# main.net
KiCad netlist of a schematic drawn in Altium Designer
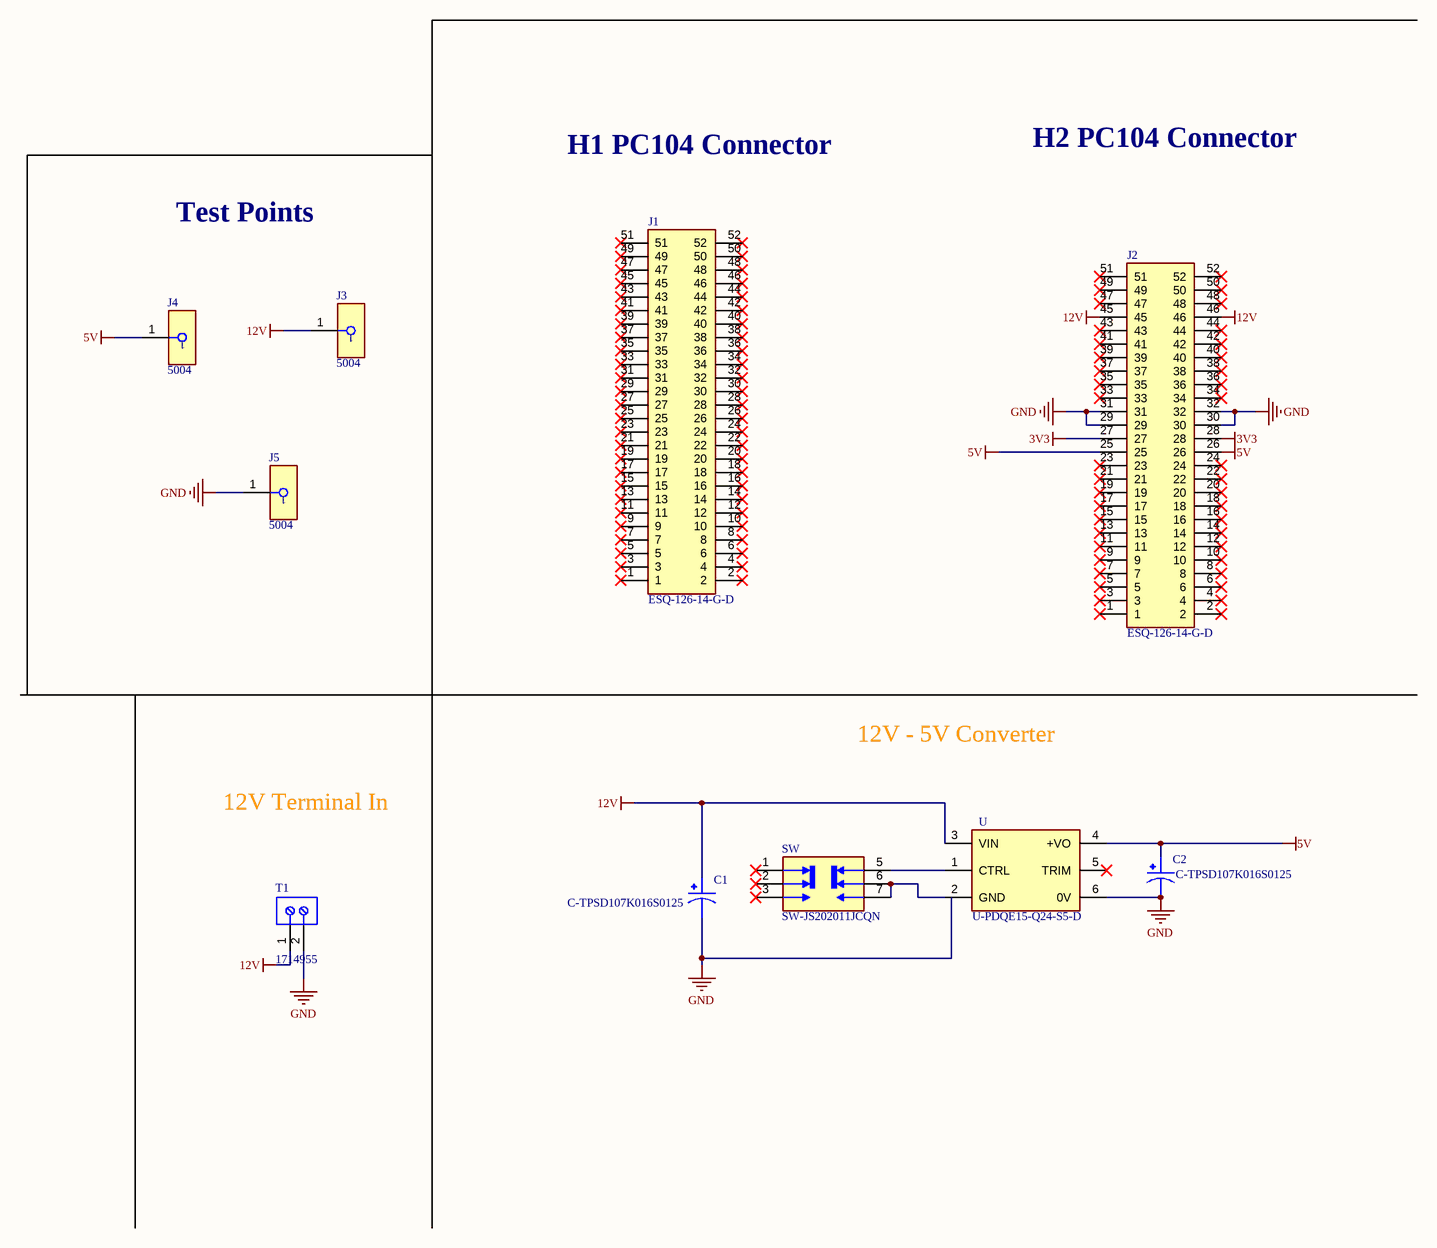
[diagram p0: main.SchDoc]

(export (version "E")
  (design (tool "Eeschema 10.0.6"))
  (components
    (comp (ref "C1")
      (value "C-TPSD107K016S0125")
      (footprint "C-TPSD107K016S0125")
      (description "CAP TANT 100UF 10% 16V 2917")
      (fields (field (name "MANUFACTURER") "KYOCERA AVX") (field (name "DIGI-KEY PART #") "478-9141-1-ND"))
      (libsource (lib "Netra_OBC_aux_power_board") (part "C-TPSD107K016S0125"))
    )
    (comp (ref "C2")
      (value "C-TPSD107K016S0125")
      (footprint "C-TPSD107K016S0125")
      (description "CAP TANT 100UF 10% 16V 2917")
      (fields (field (name "MANUFACTURER") "KYOCERA AVX") (field (name "DIGI-KEY PART #") "478-9141-1-ND"))
      (libsource (lib "Netra_OBC_aux_power_board") (part "C-TPSD107K016S0125"))
    )
    (comp (ref "J1")
      (value "ESQ-126-14-G-D")
      (footprint "SAMTEC_ESQ-126-14-G-D")
      (description "CONN SOCKET 52POS 0.1 GOLD PCB")
      (fields (field (name "MANUFACTURER") "Samtec Inc.") (field (name "DISTRIBUTOR PART #") "SAM11114-ND"))
      (libsource (lib "Netra_OBC_aux_power_board") (part "J-ESQ-126-14-G-D"))
    )
    (comp (ref "J2")
      (value "ESQ-126-14-G-D")
      (footprint "SAMTEC_ESQ-126-14-G-D")
      (description "CONN SOCKET 52POS 0.1 GOLD PCB")
      (fields (field (name "MANUFACTURER") "Samtec Inc.") (field (name "DISTRIBUTOR PART #") "SAM11114-ND"))
      (libsource (lib "Netra_OBC_aux_power_board") (part "J-ESQ-126-14-G-D"))
    )
    (comp (ref "J3")
      (value "5004")
      (footprint "FP-5004-MFG")
      (description "PC TEST POINT MINIATURE YELLOW")
      (fields
        (field (name "MANUFACTURER") "Keystone Electronics")
        (field (name "OCTOPART") "https://octopart.com/5004-keystone-28591")
      )
      (libsource (lib "Netra_OBC_aux_power_board") (part "CMP-2000-05575-2"))
    )
    (comp (ref "J4")
      (value "5004")
      (footprint "FP-5004-MFG")
      (description "PC TEST POINT MINIATURE YELLOW")
      (fields
        (field (name "MANUFACTURER") "Keystone Electronics")
        (field (name "OCTOPART") "https://octopart.com/5004-keystone-28591")
      )
      (libsource (lib "Netra_OBC_aux_power_board") (part "CMP-2000-05575-2"))
    )
    (comp (ref "J5")
      (value "5004")
      (footprint "FP-5004-MFG")
      (description "PC TEST POINT MINIATURE YELLOW")
      (fields
        (field (name "MANUFACTURER") "Keystone Electronics")
        (field (name "OCTOPART") "https://octopart.com/5004-keystone-28591")
      )
      (libsource (lib "Netra_OBC_aux_power_board") (part "CMP-2000-05575-2"))
    )
    (comp (ref "SW")
      (value "SW-JS202011JCQN")
      (footprint "SW-JS202011JCQN")
      (description "SWITCH SLIDE DPDT 300MA 6V")
      (fields
        (field (name "DISTRIBUTOR PART #") "CKN10723CT-ND")
        (field (name "MANUFACTURER PART #") "JS202011JCQN")
      )
      (libsource (lib "Netra_OBC_aux_power_board") (part "SW-JS202011JCQN"))
    )
    (comp (ref "T1")
      (value "1714955")
      (footprint "PHOE-1714955_V")
      (description "PC Terminal Block, Pitch 6.35 mm, 1 x 2 Position, Height 21.5 mm, Tail Lenght 5.1 mm, RoHS, Bulk")
      (fields (field (name "MANUFACTURER") "Phoenix Contact"))
      (libsource (lib "Altium Content Vault") (part "CN-1P-F-TB2"))
    )
    (comp (ref "U")
      (value "U-PDQE15-Q24-S5-D")
      (footprint "U-PDQE15-Q48-D5-D")
      (description "15 W, 4:1 Input Range, Single/Dual Regulated Output, DIP, 1500 Vdc Isolation, Dc-Dc Converter")
      (fields
        (field (name "MANUFACTUER PART #") "PDQE15-Q24-S5-D")
        (field (name "DISTRIBUTOR PART #") "102-6253-ND")
      )
      (libsource (lib "Netra_OBC_aux_power_board") (part "U-PDQE15-Q24-S5-D"))
    )
  )
  (nets
    (net (code "1") (name "3V3") (class "Default")
      (node (ref "J2") (pin "27") (pinfunction "27_27") (pintype "passive"))
      (node (ref "J2") (pin "28") (pinfunction "28_28") (pintype "passive"))
    )
    (net (code "2") (name "5V") (class "Default")
      (node (ref "C2") (pin "1") (pinfunction "1_1") (pintype "passive"))
      (node (ref "J2") (pin "25") (pinfunction "25_25") (pintype "passive"))
      (node (ref "J2") (pin "26") (pinfunction "26_26") (pintype "passive"))
      (node (ref "J4") (pin "1") (pinfunction "1_1") (pintype "passive"))
      (node (ref "U") (pin "4") (pinfunction "+VO_4") (pintype "passive"))
    )
    (net (code "3") (name "12V") (class "Default")
      (node (ref "C1") (pin "1") (pinfunction "1_1") (pintype "passive"))
      (node (ref "J2") (pin "45") (pinfunction "45_45") (pintype "passive"))
      (node (ref "J2") (pin "46") (pinfunction "46_46") (pintype "passive"))
      (node (ref "J3") (pin "1") (pinfunction "1_1") (pintype "passive"))
      (node (ref "T1") (pin "1") (pinfunction "1_1") (pintype "passive"))
      (node (ref "U") (pin "3") (pinfunction "VIN_3") (pintype "passive"))
    )
    (net (code "4") (name "GND") (class "Default")
      (node (ref "C1") (pin "2") (pinfunction "2_2") (pintype "passive"))
      (node (ref "C2") (pin "2") (pinfunction "2_2") (pintype "passive"))
      (node (ref "J2") (pin "29") (pinfunction "29_29") (pintype "passive"))
      (node (ref "J2") (pin "30") (pinfunction "30_30") (pintype "passive"))
      (node (ref "J2") (pin "31") (pinfunction "31_31") (pintype "passive"))
      (node (ref "J2") (pin "32") (pinfunction "32_32") (pintype "passive"))
      (node (ref "J5") (pin "1") (pinfunction "1_1") (pintype "passive"))
      (node (ref "T1") (pin "2") (pinfunction "2_2") (pintype "passive"))
      (node (ref "U") (pin "6") (pinfunction "0V_6") (pintype "passive"))
    )
    (net (code "5") (name "Net-(U-CTRL)") (class "Default")
      (node (ref "SW") (pin "5") (pinfunction "5_5") (pintype "passive"))
      (node (ref "U") (pin "1") (pinfunction "CTRL_1") (pintype "passive"))
    )
    (net (code "6") (name "Net-(U-GND)") (class "Default")
      (node (ref "SW") (pin "6") (pinfunction "6_6") (pintype "passive"))
      (node (ref "SW") (pin "7") (pinfunction "7_7") (pintype "passive"))
      (node (ref "U") (pin "2") (pinfunction "GND_2") (pintype "passive"))
    )
    (net (code "7") (name "unconnected-(J1-Pad1)") (class "Default")
      (node (ref "J1") (pin "1") (pinfunction "1_1") (pintype "passive+no_connect"))
    )
    (net (code "8") (name "unconnected-(J1-Pad2)") (class "Default")
      (node (ref "J1") (pin "2") (pinfunction "2_2") (pintype "passive+no_connect"))
    )
    (net (code "9") (name "unconnected-(J1-Pad3)") (class "Default")
      (node (ref "J1") (pin "3") (pinfunction "3_3") (pintype "passive+no_connect"))
    )
    (net (code "10") (name "unconnected-(J1-Pad4)") (class "Default")
      (node (ref "J1") (pin "4") (pinfunction "4_4") (pintype "passive+no_connect"))
    )
    (net (code "11") (name "unconnected-(J1-Pad5)") (class "Default")
      (node (ref "J1") (pin "5") (pinfunction "5_5") (pintype "passive+no_connect"))
    )
    (net (code "12") (name "unconnected-(J1-Pad6)") (class "Default")
      (node (ref "J1") (pin "6") (pinfunction "6_6") (pintype "passive+no_connect"))
    )
    (net (code "13") (name "unconnected-(J1-Pad7)") (class "Default")
      (node (ref "J1") (pin "7") (pinfunction "7_7") (pintype "passive+no_connect"))
    )
    (net (code "14") (name "unconnected-(J1-Pad8)") (class "Default")
      (node (ref "J1") (pin "8") (pinfunction "8_8") (pintype "passive+no_connect"))
    )
    (net (code "15") (name "unconnected-(J1-Pad9)") (class "Default")
      (node (ref "J1") (pin "9") (pinfunction "9_9") (pintype "passive+no_connect"))
    )
    (net (code "16") (name "unconnected-(J1-Pad10)") (class "Default")
      (node (ref "J1") (pin "10") (pinfunction "10_10") (pintype "passive+no_connect"))
    )
    (net (code "17") (name "unconnected-(J1-Pad11)") (class "Default")
      (node (ref "J1") (pin "11") (pinfunction "11_11") (pintype "passive+no_connect"))
    )
    (net (code "18") (name "unconnected-(J1-Pad12)") (class "Default")
      (node (ref "J1") (pin "12") (pinfunction "12_12") (pintype "passive+no_connect"))
    )
    (net (code "19") (name "unconnected-(J1-Pad13)") (class "Default")
      (node (ref "J1") (pin "13") (pinfunction "13_13") (pintype "passive+no_connect"))
    )
    (net (code "20") (name "unconnected-(J1-Pad14)") (class "Default")
      (node (ref "J1") (pin "14") (pinfunction "14_14") (pintype "passive+no_connect"))
    )
    (net (code "21") (name "unconnected-(J1-Pad15)") (class "Default")
      (node (ref "J1") (pin "15") (pinfunction "15_15") (pintype "passive+no_connect"))
    )
    (net (code "22") (name "unconnected-(J1-Pad16)") (class "Default")
      (node (ref "J1") (pin "16") (pinfunction "16_16") (pintype "passive+no_connect"))
    )
    (net (code "23") (name "unconnected-(J1-Pad17)") (class "Default")
      (node (ref "J1") (pin "17") (pinfunction "17_17") (pintype "passive+no_connect"))
    )
    (net (code "24") (name "unconnected-(J1-Pad18)") (class "Default")
      (node (ref "J1") (pin "18") (pinfunction "18_18") (pintype "passive+no_connect"))
    )
    (net (code "25") (name "unconnected-(J1-Pad19)") (class "Default")
      (node (ref "J1") (pin "19") (pinfunction "19_19") (pintype "passive+no_connect"))
    )
    (net (code "26") (name "unconnected-(J1-Pad20)") (class "Default")
      (node (ref "J1") (pin "20") (pinfunction "20_20") (pintype "passive+no_connect"))
    )
    (net (code "27") (name "unconnected-(J1-Pad21)") (class "Default")
      (node (ref "J1") (pin "21") (pinfunction "21_21") (pintype "passive+no_connect"))
    )
    (net (code "28") (name "unconnected-(J1-Pad22)") (class "Default")
      (node (ref "J1") (pin "22") (pinfunction "22_22") (pintype "passive+no_connect"))
    )
    (net (code "29") (name "unconnected-(J1-Pad23)") (class "Default")
      (node (ref "J1") (pin "23") (pinfunction "23_23") (pintype "passive+no_connect"))
    )
    (net (code "30") (name "unconnected-(J1-Pad24)") (class "Default")
      (node (ref "J1") (pin "24") (pinfunction "24_24") (pintype "passive+no_connect"))
    )
    (net (code "31") (name "unconnected-(J1-Pad25)") (class "Default")
      (node (ref "J1") (pin "25") (pinfunction "25_25") (pintype "passive+no_connect"))
    )
    (net (code "32") (name "unconnected-(J1-Pad26)") (class "Default")
      (node (ref "J1") (pin "26") (pinfunction "26_26") (pintype "passive+no_connect"))
    )
    (net (code "33") (name "unconnected-(J1-Pad27)") (class "Default")
      (node (ref "J1") (pin "27") (pinfunction "27_27") (pintype "passive+no_connect"))
    )
    (net (code "34") (name "unconnected-(J1-Pad28)") (class "Default")
      (node (ref "J1") (pin "28") (pinfunction "28_28") (pintype "passive+no_connect"))
    )
    (net (code "35") (name "unconnected-(J1-Pad29)") (class "Default")
      (node (ref "J1") (pin "29") (pinfunction "29_29") (pintype "passive+no_connect"))
    )
    (net (code "36") (name "unconnected-(J1-Pad30)") (class "Default")
      (node (ref "J1") (pin "30") (pinfunction "30_30") (pintype "passive+no_connect"))
    )
    (net (code "37") (name "unconnected-(J1-Pad31)") (class "Default")
      (node (ref "J1") (pin "31") (pinfunction "31_31") (pintype "passive+no_connect"))
    )
    (net (code "38") (name "unconnected-(J1-Pad32)") (class "Default")
      (node (ref "J1") (pin "32") (pinfunction "32_32") (pintype "passive+no_connect"))
    )
    (net (code "39") (name "unconnected-(J1-Pad33)") (class "Default")
      (node (ref "J1") (pin "33") (pinfunction "33_33") (pintype "passive+no_connect"))
    )
    (net (code "40") (name "unconnected-(J1-Pad34)") (class "Default")
      (node (ref "J1") (pin "34") (pinfunction "34_34") (pintype "passive+no_connect"))
    )
    (net (code "41") (name "unconnected-(J1-Pad35)") (class "Default")
      (node (ref "J1") (pin "35") (pinfunction "35_35") (pintype "passive+no_connect"))
    )
    (net (code "42") (name "unconnected-(J1-Pad36)") (class "Default")
      (node (ref "J1") (pin "36") (pinfunction "36_36") (pintype "passive+no_connect"))
    )
    (net (code "43") (name "unconnected-(J1-Pad37)") (class "Default")
      (node (ref "J1") (pin "37") (pinfunction "37_37") (pintype "passive+no_connect"))
    )
    (net (code "44") (name "unconnected-(J1-Pad38)") (class "Default")
      (node (ref "J1") (pin "38") (pinfunction "38_38") (pintype "passive+no_connect"))
    )
    (net (code "45") (name "unconnected-(J1-Pad39)") (class "Default")
      (node (ref "J1") (pin "39") (pinfunction "39_39") (pintype "passive+no_connect"))
    )
    (net (code "46") (name "unconnected-(J1-Pad40)") (class "Default")
      (node (ref "J1") (pin "40") (pinfunction "40_40") (pintype "passive+no_connect"))
    )
    (net (code "47") (name "unconnected-(J1-Pad41)") (class "Default")
      (node (ref "J1") (pin "41") (pinfunction "41_41") (pintype "passive+no_connect"))
    )
    (net (code "48") (name "unconnected-(J1-Pad42)") (class "Default")
      (node (ref "J1") (pin "42") (pinfunction "42_42") (pintype "passive+no_connect"))
    )
    (net (code "49") (name "unconnected-(J1-Pad43)") (class "Default")
      (node (ref "J1") (pin "43") (pinfunction "43_43") (pintype "passive+no_connect"))
    )
    (net (code "50") (name "unconnected-(J1-Pad44)") (class "Default")
      (node (ref "J1") (pin "44") (pinfunction "44_44") (pintype "passive+no_connect"))
    )
    (net (code "51") (name "unconnected-(J1-Pad45)") (class "Default")
      (node (ref "J1") (pin "45") (pinfunction "45_45") (pintype "passive+no_connect"))
    )
    (net (code "52") (name "unconnected-(J1-Pad46)") (class "Default")
      (node (ref "J1") (pin "46") (pinfunction "46_46") (pintype "passive+no_connect"))
    )
    (net (code "53") (name "unconnected-(J1-Pad47)") (class "Default")
      (node (ref "J1") (pin "47") (pinfunction "47_47") (pintype "passive+no_connect"))
    )
    (net (code "54") (name "unconnected-(J1-Pad48)") (class "Default")
      (node (ref "J1") (pin "48") (pinfunction "48_48") (pintype "passive+no_connect"))
    )
    (net (code "55") (name "unconnected-(J1-Pad49)") (class "Default")
      (node (ref "J1") (pin "49") (pinfunction "49_49") (pintype "passive+no_connect"))
    )
    (net (code "56") (name "unconnected-(J1-Pad50)") (class "Default")
      (node (ref "J1") (pin "50") (pinfunction "50_50") (pintype "passive+no_connect"))
    )
    (net (code "57") (name "unconnected-(J1-Pad51)") (class "Default")
      (node (ref "J1") (pin "51") (pinfunction "51_51") (pintype "passive+no_connect"))
    )
    (net (code "58") (name "unconnected-(J1-Pad52)") (class "Default")
      (node (ref "J1") (pin "52") (pinfunction "52_52") (pintype "passive+no_connect"))
    )
    (net (code "59") (name "unconnected-(J2-Pad1)") (class "Default")
      (node (ref "J2") (pin "1") (pinfunction "1_1") (pintype "passive+no_connect"))
    )
    (net (code "60") (name "unconnected-(J2-Pad2)") (class "Default")
      (node (ref "J2") (pin "2") (pinfunction "2_2") (pintype "passive+no_connect"))
    )
    (net (code "61") (name "unconnected-(J2-Pad3)") (class "Default")
      (node (ref "J2") (pin "3") (pinfunction "3_3") (pintype "passive+no_connect"))
    )
    (net (code "62") (name "unconnected-(J2-Pad4)") (class "Default")
      (node (ref "J2") (pin "4") (pinfunction "4_4") (pintype "passive+no_connect"))
    )
    (net (code "63") (name "unconnected-(J2-Pad5)") (class "Default")
      (node (ref "J2") (pin "5") (pinfunction "5_5") (pintype "passive+no_connect"))
    )
    (net (code "64") (name "unconnected-(J2-Pad6)") (class "Default")
      (node (ref "J2") (pin "6") (pinfunction "6_6") (pintype "passive+no_connect"))
    )
    (net (code "65") (name "unconnected-(J2-Pad7)") (class "Default")
      (node (ref "J2") (pin "7") (pinfunction "7_7") (pintype "passive+no_connect"))
    )
    (net (code "66") (name "unconnected-(J2-Pad8)") (class "Default")
      (node (ref "J2") (pin "8") (pinfunction "8_8") (pintype "passive+no_connect"))
    )
    (net (code "67") (name "unconnected-(J2-Pad9)") (class "Default")
      (node (ref "J2") (pin "9") (pinfunction "9_9") (pintype "passive+no_connect"))
    )
    (net (code "68") (name "unconnected-(J2-Pad10)") (class "Default")
      (node (ref "J2") (pin "10") (pinfunction "10_10") (pintype "passive+no_connect"))
    )
    (net (code "69") (name "unconnected-(J2-Pad11)") (class "Default")
      (node (ref "J2") (pin "11") (pinfunction "11_11") (pintype "passive+no_connect"))
    )
    (net (code "70") (name "unconnected-(J2-Pad12)") (class "Default")
      (node (ref "J2") (pin "12") (pinfunction "12_12") (pintype "passive+no_connect"))
    )
    (net (code "71") (name "unconnected-(J2-Pad13)") (class "Default")
      (node (ref "J2") (pin "13") (pinfunction "13_13") (pintype "passive+no_connect"))
    )
    (net (code "72") (name "unconnected-(J2-Pad14)") (class "Default")
      (node (ref "J2") (pin "14") (pinfunction "14_14") (pintype "passive+no_connect"))
    )
    (net (code "73") (name "unconnected-(J2-Pad15)") (class "Default")
      (node (ref "J2") (pin "15") (pinfunction "15_15") (pintype "passive+no_connect"))
    )
    (net (code "74") (name "unconnected-(J2-Pad16)") (class "Default")
      (node (ref "J2") (pin "16") (pinfunction "16_16") (pintype "passive+no_connect"))
    )
    (net (code "75") (name "unconnected-(J2-Pad17)") (class "Default")
      (node (ref "J2") (pin "17") (pinfunction "17_17") (pintype "passive+no_connect"))
    )
    (net (code "76") (name "unconnected-(J2-Pad18)") (class "Default")
      (node (ref "J2") (pin "18") (pinfunction "18_18") (pintype "passive+no_connect"))
    )
    (net (code "77") (name "unconnected-(J2-Pad19)") (class "Default")
      (node (ref "J2") (pin "19") (pinfunction "19_19") (pintype "passive+no_connect"))
    )
    (net (code "78") (name "unconnected-(J2-Pad20)") (class "Default")
      (node (ref "J2") (pin "20") (pinfunction "20_20") (pintype "passive+no_connect"))
    )
    (net (code "79") (name "unconnected-(J2-Pad21)") (class "Default")
      (node (ref "J2") (pin "21") (pinfunction "21_21") (pintype "passive+no_connect"))
    )
    (net (code "80") (name "unconnected-(J2-Pad22)") (class "Default")
      (node (ref "J2") (pin "22") (pinfunction "22_22") (pintype "passive+no_connect"))
    )
    (net (code "81") (name "unconnected-(J2-Pad23)") (class "Default")
      (node (ref "J2") (pin "23") (pinfunction "23_23") (pintype "passive+no_connect"))
    )
    (net (code "82") (name "unconnected-(J2-Pad24)") (class "Default")
      (node (ref "J2") (pin "24") (pinfunction "24_24") (pintype "passive+no_connect"))
    )
    (net (code "83") (name "unconnected-(J2-Pad33)") (class "Default")
      (node (ref "J2") (pin "33") (pinfunction "33_33") (pintype "passive+no_connect"))
    )
    (net (code "84") (name "unconnected-(J2-Pad34)") (class "Default")
      (node (ref "J2") (pin "34") (pinfunction "34_34") (pintype "passive+no_connect"))
    )
    (net (code "85") (name "unconnected-(J2-Pad35)") (class "Default")
      (node (ref "J2") (pin "35") (pinfunction "35_35") (pintype "passive+no_connect"))
    )
    (net (code "86") (name "unconnected-(J2-Pad36)") (class "Default")
      (node (ref "J2") (pin "36") (pinfunction "36_36") (pintype "passive+no_connect"))
    )
    (net (code "87") (name "unconnected-(J2-Pad37)") (class "Default")
      (node (ref "J2") (pin "37") (pinfunction "37_37") (pintype "passive+no_connect"))
    )
    (net (code "88") (name "unconnected-(J2-Pad38)") (class "Default")
      (node (ref "J2") (pin "38") (pinfunction "38_38") (pintype "passive+no_connect"))
    )
    (net (code "89") (name "unconnected-(J2-Pad39)") (class "Default")
      (node (ref "J2") (pin "39") (pinfunction "39_39") (pintype "passive+no_connect"))
    )
    (net (code "90") (name "unconnected-(J2-Pad40)") (class "Default")
      (node (ref "J2") (pin "40") (pinfunction "40_40") (pintype "passive+no_connect"))
    )
    (net (code "91") (name "unconnected-(J2-Pad41)") (class "Default")
      (node (ref "J2") (pin "41") (pinfunction "41_41") (pintype "passive+no_connect"))
    )
    (net (code "92") (name "unconnected-(J2-Pad42)") (class "Default")
      (node (ref "J2") (pin "42") (pinfunction "42_42") (pintype "passive+no_connect"))
    )
    (net (code "93") (name "unconnected-(J2-Pad43)") (class "Default")
      (node (ref "J2") (pin "43") (pinfunction "43_43") (pintype "passive+no_connect"))
    )
    (net (code "94") (name "unconnected-(J2-Pad44)") (class "Default")
      (node (ref "J2") (pin "44") (pinfunction "44_44") (pintype "passive+no_connect"))
    )
    (net (code "95") (name "unconnected-(J2-Pad47)") (class "Default")
      (node (ref "J2") (pin "47") (pinfunction "47_47") (pintype "passive+no_connect"))
    )
    (net (code "96") (name "unconnected-(J2-Pad48)") (class "Default")
      (node (ref "J2") (pin "48") (pinfunction "48_48") (pintype "passive+no_connect"))
    )
    (net (code "97") (name "unconnected-(J2-Pad49)") (class "Default")
      (node (ref "J2") (pin "49") (pinfunction "49_49") (pintype "passive+no_connect"))
    )
    (net (code "98") (name "unconnected-(J2-Pad50)") (class "Default")
      (node (ref "J2") (pin "50") (pinfunction "50_50") (pintype "passive+no_connect"))
    )
    (net (code "99") (name "unconnected-(J2-Pad51)") (class "Default")
      (node (ref "J2") (pin "51") (pinfunction "51_51") (pintype "passive+no_connect"))
    )
    (net (code "100") (name "unconnected-(J2-Pad52)") (class "Default")
      (node (ref "J2") (pin "52") (pinfunction "52_52") (pintype "passive+no_connect"))
    )
    (net (code "101") (name "unconnected-(SW-Pad1)") (class "Default")
      (node (ref "SW") (pin "1") (pinfunction "1_1") (pintype "passive+no_connect"))
    )
    (net (code "102") (name "unconnected-(SW-Pad2)") (class "Default")
      (node (ref "SW") (pin "2") (pinfunction "2_2") (pintype "passive+no_connect"))
    )
    (net (code "103") (name "unconnected-(SW-Pad3)") (class "Default")
      (node (ref "SW") (pin "3") (pinfunction "3_3") (pintype "passive+no_connect"))
    )
    (net (code "104") (name "unconnected-(U-TRIM-Pad5)") (class "Default")
      (node (ref "U") (pin "5") (pinfunction "TRIM_5") (pintype "passive+no_connect"))
    )
  )
)
